# Motors.net
KiCad netlist of a schematic drawn in Altium Designer
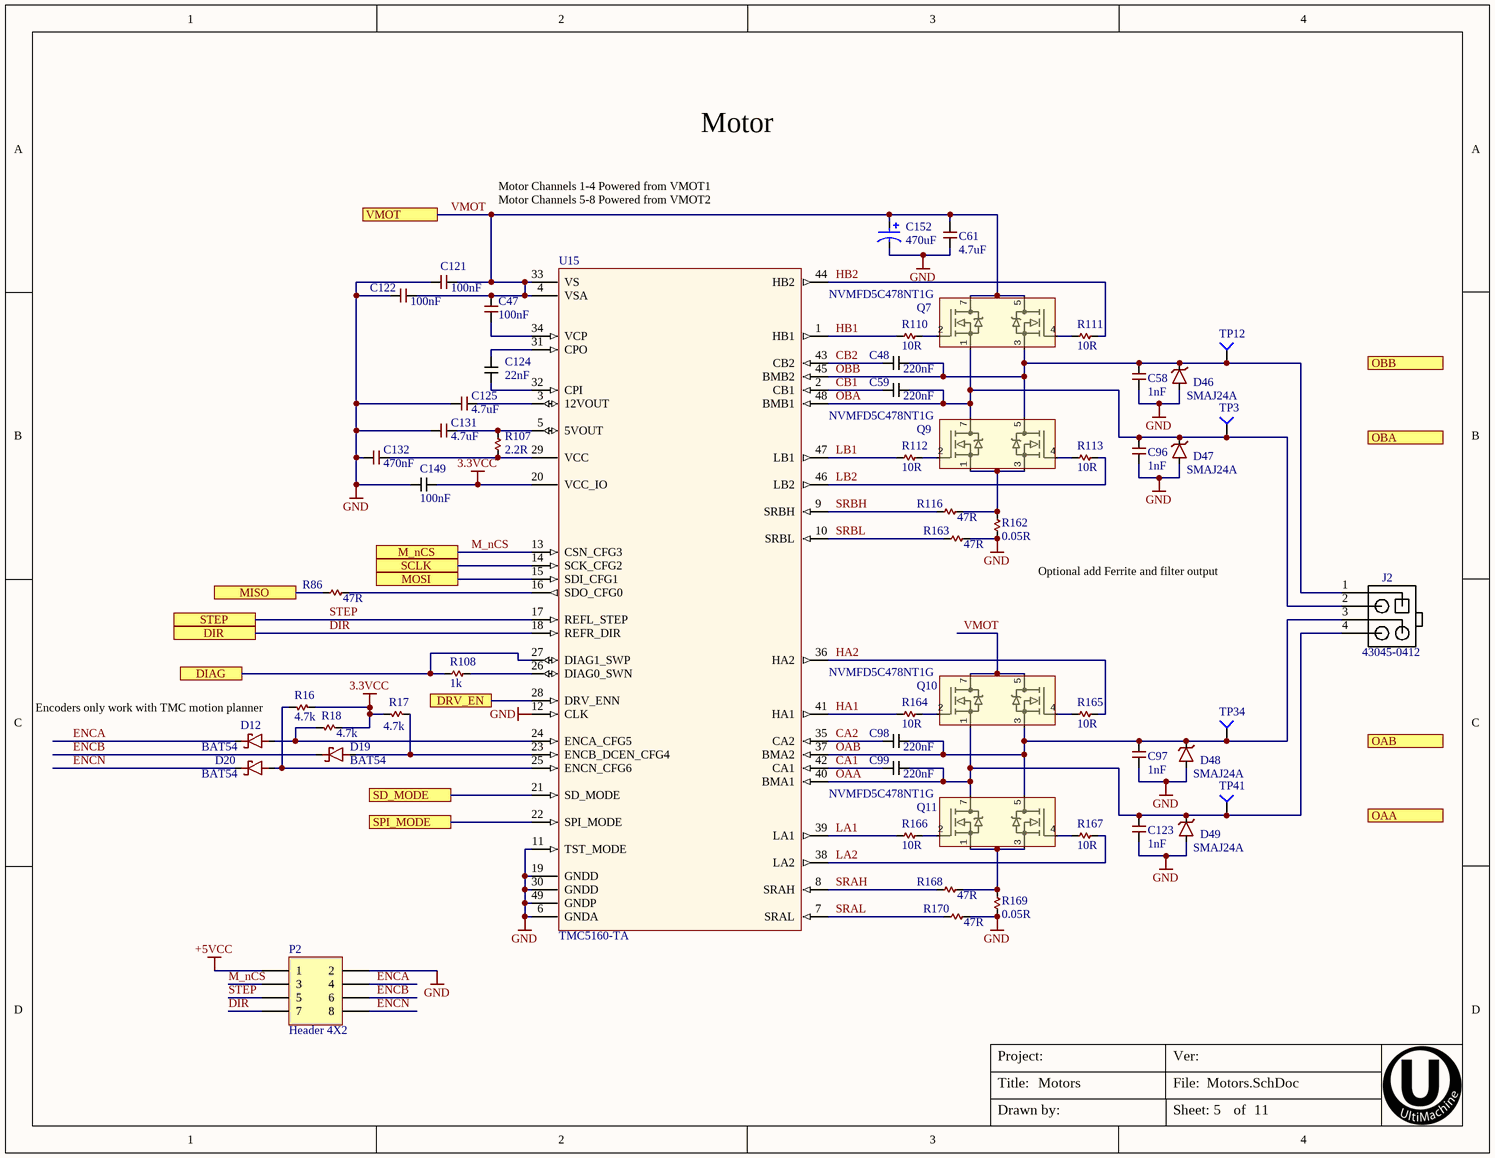
[diagram p0: Motors.SchDoc]

(export (version "E")
  (design (tool "Eeschema 10.0.6"))
  (components
    (comp (ref "C47")
      (value "100nF")
      (footprint "C0603")
      (description "CAP CER 0603 100nF 50V 10% X7R")
      (fields (field (name "MANUFACTURER") "Kemet") (field (name "PART") "C0603C104K5RACTU"))
      (libsource (lib "Capacitors") (part "100nF 0603 50V X7R"))
    )
    (comp (ref "C48")
      (value "220nF")
      (footprint "C0603")
      (description "CAP CER 0.22UF 50V X7R 0603")
      (fields (field (name "MANUFACTURER") "TDK") (field (name "PART") "CGA3E3X7R1H224K080AB"))
      (libsource (lib "Capacitors") (part "220nF 50V X7R 0603"))
    )
    (comp (ref "C58")
      (value "1nF")
      (footprint "C0603")
      (description "CAP CER 0603  1nF 50v 10% X7R")
      (fields (field (name "MANUFACTURER") "Kemet") (field (name "PART") "C0603C102K5RACTU"))
      (libsource (lib "Capacitors") (part "1nF 50V X7R 0603"))
    )
    (comp (ref "C59")
      (value "220nF")
      (footprint "C0603")
      (description "CAP CER 0.22UF 50V X7R 0603")
      (fields (field (name "MANUFACTURER") "TDK") (field (name "PART") "CGA3E3X7R1H224K080AB"))
      (libsource (lib "Capacitors") (part "220nF 50V X7R 0603"))
    )
    (comp (ref "C61")
      (value "4.7uF")
      (footprint "C1206")
      (description "CAP CER 1206 4.7uF 50V 10% X5R")
      (fields (field (name "MANUFACTURER") "Kemet") (field (name "PART") "C1206C475K5PACTU"))
      (libsource (lib "Capacitors") (part "4.7uF 1206 50V X5R"))
    )
    (comp (ref "C96")
      (value "1nF")
      (footprint "C0603")
      (description "CAP CER 0603  1nF 50v 10% X7R")
      (fields (field (name "MANUFACTURER") "Kemet") (field (name "PART") "C0603C102K5RACTU"))
      (libsource (lib "Capacitors") (part "1nF 50V X7R 0603"))
    )
    (comp (ref "C97")
      (value "1nF")
      (footprint "C0603")
      (description "CAP CER 0603  1nF 50v 10% X7R")
      (fields (field (name "MANUFACTURER") "Kemet") (field (name "PART") "C0603C102K5RACTU"))
      (libsource (lib "Capacitors") (part "1nF 50V X7R 0603"))
    )
    (comp (ref "C98")
      (value "220nF")
      (footprint "C0603")
      (description "CAP CER 0.22UF 50V X7R 0603")
      (fields (field (name "MANUFACTURER") "TDK") (field (name "PART") "CGA3E3X7R1H224K080AB"))
      (libsource (lib "Capacitors") (part "220nF 50V X7R 0603"))
    )
    (comp (ref "C99")
      (value "220nF")
      (footprint "C0603")
      (description "CAP CER 0.22UF 50V X7R 0603")
      (fields (field (name "MANUFACTURER") "TDK") (field (name "PART") "CGA3E3X7R1H224K080AB"))
      (libsource (lib "Capacitors") (part "220nF 50V X7R 0603"))
    )
    (comp (ref "C121")
      (value "100nF")
      (footprint "C0603")
      (description "CAP CER 0603 100nF 50V 10% X7R")
      (fields (field (name "MANUFACTURER") "Kemet") (field (name "PART") "C0603C104K5RACTU"))
      (libsource (lib "Capacitors") (part "100nF 0603 50V X7R"))
    )
    (comp (ref "C122")
      (value "100nF")
      (footprint "C0603")
      (description "CAP CER 0603 100nF 50V 10% X7R")
      (fields (field (name "MANUFACTURER") "Kemet") (field (name "PART") "C0603C104K5RACTU"))
      (libsource (lib "Capacitors") (part "100nF 0603 50V X7R"))
    )
    (comp (ref "C123")
      (value "1nF")
      (footprint "C0603")
      (description "CAP CER 0603  1nF 50v 10% X7R")
      (fields (field (name "MANUFACTURER") "Kemet") (field (name "PART") "C0603C102K5RACTU"))
      (libsource (lib "Capacitors") (part "1nF 50V X7R 0603"))
    )
    (comp (ref "C124")
      (value "22nF")
      (footprint "C0603")
      (description "CAP CER 0.022UF 100V X7R 0603")
      (fields (field (name "MANUFACTURER") "Kemet") (field (name "PART") "C0603C223K1RACTU"))
      (libsource (lib "Capacitors") (part "22nF 100V X7R 0603"))
    )
    (comp (ref "C125")
      (value "4.7uF")
      (footprint "C1206")
      (description "CAP CER 1206 4.7uF 50V 10% X5R")
      (fields (field (name "MANUFACTURER") "Kemet") (field (name "PART") "C1206C475K5PACTU"))
      (libsource (lib "Capacitors") (part "4.7uF 1206 50V X5R"))
    )
    (comp (ref "C131")
      (value "4.7uF")
      (footprint "C0603")
      (description "CAP CER 4.7UF 6.3V X7R 0603")
      (fields (field (name "MANUFACTURER") "Samsung") (field (name "PART") "CL10B475KQ8NQNC"))
      (libsource (lib "Capacitors") (part "4.7uF 0603 6.3V X7R"))
    )
    (comp (ref "C132")
      (value "470nF")
      (footprint "C0402")
      (description "470nF 6.3v C0402 - GRM155R60J474KE19D")
      (fields (field (name "TOLERANCE") "10%") (field (name "MANUFACTURER") "Murata"))
      (libsource (lib "Capacitors") (part "470nF 0402 6.3V X5R"))
    )
    (comp (ref "C149")
      (value "100nF")
      (footprint "C0201 Large Pads")
      (description "CAP CER 0.1UF 6.3V 10% X5R 0201")
      (fields (field (name "MANUFACTURER") "Samsung") (field (name "TOLERANCE") "10%"))
      (libsource (lib "Capacitors") (part "100nF 6.3V X5R 0201"))
    )
    (comp (ref "C152")
      (value "470uF")
      (footprint "CAP16x17")
      (description "CAP ALUM 470UF 20% 50V SMD")
      (fields (field (name "MANUFACTURER") "Nichicon") (field (name "PART") "UCZ1H471MNQ1MS"))
      (libsource (lib "Capacitors") (part "470uF Al-El 50V 80mOhms 16-18mmD"))
    )
    (comp (ref "D12")
      (value "BAT54")
      (footprint "SOD523_IPC")
      (description "DIODE SCHOTTKY 30V 200MA SOD523")
      (fields (field (name "MANUFACTURER") "Diodes Incorporated") (field (name "PART") "BAT54WX-TP"))
      (libsource (lib "Diodes") (part "BAT54WX"))
    )
    (comp (ref "D19")
      (value "BAT54")
      (footprint "SOD523_IPC")
      (description "DIODE SCHOTTKY 30V 200MA SOD523")
      (fields (field (name "MANUFACTURER") "Diodes Incorporated") (field (name "PART") "BAT54WX-TP"))
      (libsource (lib "Diodes") (part "BAT54WX"))
    )
    (comp (ref "D20")
      (value "BAT54")
      (footprint "SOD523_IPC")
      (description "DIODE SCHOTTKY 30V 200MA SOD523")
      (fields (field (name "MANUFACTURER") "Diodes Incorporated") (field (name "PART") "BAT54WX-TP"))
      (libsource (lib "Diodes") (part "BAT54WX"))
    )
    (comp (ref "D46")
      (value "SMAJ24A")
      (footprint "SMA-SM")
      (description "TVS DIODE 24V 38.9V SMA")
      (fields (field (name "MANUFACTURER") "Bourns Inc"))
      (libsource (lib "Diodes") (part "SMAJ24A"))
    )
    (comp (ref "D47")
      (value "SMAJ24A")
      (footprint "SMA-SM")
      (description "TVS DIODE 24V 38.9V SMA")
      (fields (field (name "MANUFACTURER") "Bourns Inc"))
      (libsource (lib "Diodes") (part "SMAJ24A"))
    )
    (comp (ref "D48")
      (value "SMAJ24A")
      (footprint "SMA-SM")
      (description "TVS DIODE 24V 38.9V SMA")
      (fields (field (name "MANUFACTURER") "Bourns Inc"))
      (libsource (lib "Diodes") (part "SMAJ24A"))
    )
    (comp (ref "D49")
      (value "SMAJ24A")
      (footprint "SMA-SM")
      (description "TVS DIODE 24V 38.9V SMA")
      (fields (field (name "MANUFACTURER") "Bourns Inc"))
      (libsource (lib "Diodes") (part "SMAJ24A"))
    )
    (comp (ref "J2")
      (value "43045-0412")
      (footprint "43045-0412")
      (description "Conn - 3mm Pitch Fixed")
      (fields (field (name "MANUFACTURER") "Molex"))
      (libsource (lib "Connectors") (part "Micro-Fit THT 4pos 3mm"))
    )
    (comp (ref "P2")
      (value "Header 4X2")
      (footprint "HDR2X4")
      (description "Header, 4-Pin, Dual row")
      (fields (field (name "PUBLISHER") "Altium Limited"))
      (libsource (lib "Miscellaneous Connectors") (part "Header 4X2"))
    )
    (comp (ref "Q7")
      (value "NVMFD5C478NT1G")
      (footprint "SO8FL-Dual (DFN8 5x6, 1.26P Dual Flag)")
      (description "40V 17 MOHM T6 S08FL DUAL")
      (fields (field (name "MANUFACTURER") "ON Semiconductor") (field (name "TOLERANCE") "-NA-"))
      (libsource (lib "Transistors") (part "NVMFD5C478NT1G"))
    )
    (comp (ref "Q9")
      (value "NVMFD5C478NT1G")
      (footprint "SO8FL-Dual (DFN8 5x6, 1.26P Dual Flag)")
      (description "40V 17 MOHM T6 S08FL DUAL")
      (fields (field (name "MANUFACTURER") "ON Semiconductor") (field (name "TOLERANCE") "-NA-"))
      (libsource (lib "Transistors") (part "NVMFD5C478NT1G"))
    )
    (comp (ref "Q10")
      (value "NVMFD5C478NT1G")
      (footprint "SO8FL-Dual (DFN8 5x6, 1.26P Dual Flag)")
      (description "40V 17 MOHM T6 S08FL DUAL")
      (fields (field (name "MANUFACTURER") "ON Semiconductor") (field (name "TOLERANCE") "-NA-"))
      (libsource (lib "Transistors") (part "NVMFD5C478NT1G"))
    )
    (comp (ref "Q11")
      (value "NVMFD5C478NT1G")
      (footprint "SO8FL-Dual (DFN8 5x6, 1.26P Dual Flag)")
      (description "40V 17 MOHM T6 S08FL DUAL")
      (fields (field (name "MANUFACTURER") "ON Semiconductor") (field (name "TOLERANCE") "-NA-"))
      (libsource (lib "Transistors") (part "NVMFD5C478NT1G"))
    )
    (comp (ref "R16")
      (value "4.7k")
      (footprint "R0402")
      (description "RES SMD 4.7K OHM 1% 1/16W 0402")
      (fields (field (name "MANUFACTURER") "YAGEO") (field (name "PART") "RC0402FR-074K7L"))
      (libsource (lib "Resistors") (part "4.7k 1% 0402"))
    )
    (comp (ref "R17")
      (value "4.7k")
      (footprint "R0402")
      (description "RES SMD 4.7K OHM 1% 1/16W 0402")
      (fields (field (name "MANUFACTURER") "YAGEO") (field (name "PART") "RC0402FR-074K7L"))
      (libsource (lib "Resistors") (part "4.7k 1% 0402"))
    )
    (comp (ref "R18")
      (value "4.7k")
      (footprint "R0402")
      (description "RES SMD 4.7K OHM 1% 1/16W 0402")
      (fields (field (name "MANUFACTURER") "YAGEO") (field (name "PART") "RC0402FR-074K7L"))
      (libsource (lib "Resistors") (part "4.7k 1% 0402"))
    )
    (comp (ref "R86")
      (value "47R")
      (footprint "R0402")
      (description "RES 47 OHM 1% 1/16W 0402")
      (fields (field (name "MANUFACTURER") "Vishay Dale") (field (name "TOLERANCE") "+/- 1%"))
      (libsource (lib "Resistors") (part "47R 1% 0402"))
    )
    (comp (ref "R107")
      (value "2.2R")
      (footprint "R0402")
      (description "RES SMD 2.2 OHM 5% 1/16W 0402")
      (fields (field (name "MANUFACTURER") "Yageo") (field (name "TOLERANCE") "+/- 5%"))
      (libsource (lib "Resistors") (part "2.2R 5% 0402"))
    )
    (comp (ref "R108")
      (value "1k")
      (footprint "R0402")
      (description "RES 0402 1k 63mW 1%")
      (fields (field (name "MANUFACTURER") "Yageo") (field (name "PART") "RC0402FR-071KL"))
      (libsource (lib "Resistors") (part "1k 1% 0402"))
    )
    (comp (ref "R110")
      (value "10R")
      (footprint "R0402")
      (description "RES SMD 10 OHM 1% 1/16W 0402")
      (fields (field (name "MANUFACTURER") "Yageo") (field (name "PART") "RC0402FR-0710RL"))
      (libsource (lib "Resistors") (part "10R 1% 0402"))
    )
    (comp (ref "R111")
      (value "10R")
      (footprint "R0402")
      (description "RES SMD 10 OHM 1% 1/16W 0402")
      (fields (field (name "MANUFACTURER") "Yageo") (field (name "PART") "RC0402FR-0710RL"))
      (libsource (lib "Resistors") (part "10R 1% 0402"))
    )
    (comp (ref "R112")
      (value "10R")
      (footprint "R0402")
      (description "RES SMD 10 OHM 1% 1/16W 0402")
      (fields (field (name "MANUFACTURER") "Yageo") (field (name "PART") "RC0402FR-0710RL"))
      (libsource (lib "Resistors") (part "10R 1% 0402"))
    )
    (comp (ref "R113")
      (value "10R")
      (footprint "R0402")
      (description "RES SMD 10 OHM 1% 1/16W 0402")
      (fields (field (name "MANUFACTURER") "Yageo") (field (name "PART") "RC0402FR-0710RL"))
      (libsource (lib "Resistors") (part "10R 1% 0402"))
    )
    (comp (ref "R116")
      (value "47R")
      (footprint "R0402")
      (description "RES 47 OHM 1% 1/16W 0402")
      (fields (field (name "MANUFACTURER") "Vishay Dale") (field (name "TOLERANCE") "+/- 1%"))
      (libsource (lib "Resistors") (part "47R 1% 0402"))
    )
    (comp (ref "R162")
      (value "0.05R")
      (footprint "R2512")
      (description "RES 0.05 OHM 1% 2W 2512")
      (fields (field (name "MANUFACTURER") "Stackpole") (field (name "TOLERANCE") "+/- 1%"))
      (libsource (lib "Resistors") (part "0.05R 1% 2512"))
    )
    (comp (ref "R163")
      (value "47R")
      (footprint "R0402")
      (description "RES 47 OHM 1% 1/16W 0402")
      (fields (field (name "MANUFACTURER") "Vishay Dale") (field (name "TOLERANCE") "+/- 1%"))
      (libsource (lib "Resistors") (part "47R 1% 0402"))
    )
    (comp (ref "R164")
      (value "10R")
      (footprint "R0402")
      (description "RES SMD 10 OHM 1% 1/16W 0402")
      (fields (field (name "MANUFACTURER") "Yageo") (field (name "PART") "RC0402FR-0710RL"))
      (libsource (lib "Resistors") (part "10R 1% 0402"))
    )
    (comp (ref "R165")
      (value "10R")
      (footprint "R0402")
      (description "RES SMD 10 OHM 1% 1/16W 0402")
      (fields (field (name "MANUFACTURER") "Yageo") (field (name "PART") "RC0402FR-0710RL"))
      (libsource (lib "Resistors") (part "10R 1% 0402"))
    )
    (comp (ref "R166")
      (value "10R")
      (footprint "R0402")
      (description "RES SMD 10 OHM 1% 1/16W 0402")
      (fields (field (name "MANUFACTURER") "Yageo") (field (name "PART") "RC0402FR-0710RL"))
      (libsource (lib "Resistors") (part "10R 1% 0402"))
    )
    (comp (ref "R167")
      (value "10R")
      (footprint "R0402")
      (description "RES SMD 10 OHM 1% 1/16W 0402")
      (fields (field (name "MANUFACTURER") "Yageo") (field (name "PART") "RC0402FR-0710RL"))
      (libsource (lib "Resistors") (part "10R 1% 0402"))
    )
    (comp (ref "R168")
      (value "47R")
      (footprint "R0402")
      (description "RES 47 OHM 1% 1/16W 0402")
      (fields (field (name "MANUFACTURER") "Vishay Dale") (field (name "TOLERANCE") "+/- 1%"))
      (libsource (lib "Resistors") (part "47R 1% 0402"))
    )
    (comp (ref "R169")
      (value "0.05R")
      (footprint "R2512")
      (description "RES 0.05 OHM 1% 2W 2512")
      (fields (field (name "MANUFACTURER") "Stackpole") (field (name "TOLERANCE") "+/- 1%"))
      (libsource (lib "Resistors") (part "0.05R 1% 2512"))
    )
    (comp (ref "R170")
      (value "47R")
      (footprint "R0402")
      (description "RES 47 OHM 1% 1/16W 0402")
      (fields (field (name "MANUFACTURER") "Vishay Dale") (field (name "TOLERANCE") "+/- 1%"))
      (libsource (lib "Resistors") (part "47R 1% 0402"))
    )
    (comp (ref "TP3")
      (value "TP4")
      (footprint "TP-2")
      (description "Socket")
      (fields (field (name "PART") "NOTAPART-Testpoint"))
      (libsource (lib "Archim") (part "Socket"))
    )
    (comp (ref "TP12")
      (value "TP4")
      (footprint "TP-2")
      (description "Socket")
      (fields (field (name "PART") "NOTAPART-Testpoint"))
      (libsource (lib "Archim") (part "Socket"))
    )
    (comp (ref "TP34")
      (value "TP4")
      (footprint "TP-2")
      (description "Socket")
      (fields (field (name "PART") "NOTAPART-Testpoint"))
      (libsource (lib "Archim") (part "Socket"))
    )
    (comp (ref "TP41")
      (value "TP4")
      (footprint "TP-2")
      (description "Socket")
      (fields (field (name "PART") "NOTAPART-Testpoint"))
      (libsource (lib "Archim") (part "Socket"))
    )
    (comp (ref "U15")
      (value "TMC5160-TA")
      (footprint "TQFP48-EP")
      (description "IC STEPPER MOTOR DVR TQFP48-EP")
      (fields (field (name "MANUFACTURER") "Trinamic"))
      (libsource (lib "ICs-Motor Controller") (part "TMC5160-TA"))
    )
  )
  (nets
    (net (code "1") (name "+5VCC") (class "Default")
      (node (ref "P2") (pin "1") (pinfunction "1_1") (pintype "passive"))
    )
    (net (code "2") (name "/CA1") (class "Default")
      (node (ref "C99") (pin "1") (pinfunction "1_1") (pintype "passive"))
      (node (ref "U15") (pin "42") (pinfunction "CA1_42") (pintype "input"))
    )
    (net (code "3") (name "/CA2") (class "Default")
      (node (ref "C98") (pin "1") (pinfunction "1_1") (pintype "passive"))
      (node (ref "U15") (pin "35") (pinfunction "CA2_35") (pintype "input"))
    )
    (net (code "4") (name "/CB1") (class "Default")
      (node (ref "C59") (pin "1") (pinfunction "1_1") (pintype "passive"))
      (node (ref "U15") (pin "2") (pinfunction "CB1_2") (pintype "input"))
    )
    (net (code "5") (name "/CB2") (class "Default")
      (node (ref "C48") (pin "1") (pinfunction "1_1") (pintype "passive"))
      (node (ref "U15") (pin "43") (pinfunction "CB2_43") (pintype "input"))
    )
    (net (code "6") (name "/DIAG") (class "Default")
      (node (ref "R108") (pin "2") (pinfunction "2_2") (pintype "passive"))
      (node (ref "U15") (pin "27") (pinfunction "DIAG1_SWP_27") (pintype "bidirectional"))
    )
    (net (code "7") (name "/DIR") (class "Default")
      (node (ref "P2") (pin "7") (pinfunction "7_7") (pintype "passive"))
      (node (ref "U15") (pin "18") (pinfunction "REFR_DIR_18") (pintype "input"))
    )
    (net (code "8") (name "/DRV_EN") (class "Default")
      (node (ref "U15") (pin "28") (pinfunction "DRV_ENN_28") (pintype "input"))
    )
    (net (code "9") (name "/ENCA") (class "Default")
      (node (ref "D12") (pin "K") (pinfunction "K_K") (pintype "passive"))
      (node (ref "P2") (pin "4") (pinfunction "4_4") (pintype "passive"))
    )
    (net (code "10") (name "/ENCB") (class "Default")
      (node (ref "D19") (pin "K") (pinfunction "K_K") (pintype "passive"))
      (node (ref "P2") (pin "6") (pinfunction "6_6") (pintype "passive"))
    )
    (net (code "11") (name "/ENCN") (class "Default")
      (node (ref "D20") (pin "K") (pinfunction "K_K") (pintype "passive"))
      (node (ref "P2") (pin "8") (pinfunction "8_8") (pintype "passive"))
    )
    (net (code "12") (name "/HA1") (class "Default")
      (node (ref "R164") (pin "1") (pinfunction "1_1") (pintype "passive"))
      (node (ref "U15") (pin "41") (pinfunction "HA1_41") (pintype "output"))
    )
    (net (code "13") (name "/HA2") (class "Default")
      (node (ref "R165") (pin "2") (pinfunction "2_2") (pintype "passive"))
      (node (ref "U15") (pin "36") (pinfunction "HA2_36") (pintype "output"))
    )
    (net (code "14") (name "/HB1") (class "Default")
      (node (ref "R110") (pin "1") (pinfunction "1_1") (pintype "passive"))
      (node (ref "U15") (pin "1") (pinfunction "HB1_1") (pintype "output"))
    )
    (net (code "15") (name "/HB2") (class "Default")
      (node (ref "R111") (pin "2") (pinfunction "2_2") (pintype "passive"))
      (node (ref "U15") (pin "44") (pinfunction "HB2_44") (pintype "output"))
    )
    (net (code "16") (name "/LA1") (class "Default")
      (node (ref "R166") (pin "1") (pinfunction "1_1") (pintype "passive"))
      (node (ref "U15") (pin "39") (pinfunction "LA1_39") (pintype "output"))
    )
    (net (code "17") (name "/LA2") (class "Default")
      (node (ref "R167") (pin "2") (pinfunction "2_2") (pintype "passive"))
      (node (ref "U15") (pin "38") (pinfunction "LA2_38") (pintype "output"))
    )
    (net (code "18") (name "/LB1") (class "Default")
      (node (ref "R112") (pin "1") (pinfunction "1_1") (pintype "passive"))
      (node (ref "U15") (pin "47") (pinfunction "LB1_47") (pintype "output"))
    )
    (net (code "19") (name "/LB2") (class "Default")
      (node (ref "R113") (pin "2") (pinfunction "2_2") (pintype "passive"))
      (node (ref "U15") (pin "46") (pinfunction "LB2_46") (pintype "output"))
    )
    (net (code "20") (name "/MISO") (class "Default")
      (node (ref "R86") (pin "1") (pinfunction "1_1") (pintype "passive"))
    )
    (net (code "21") (name "/MOSI") (class "Default")
      (node (ref "U15") (pin "15") (pinfunction "SDI_CFG1_15") (pintype "input"))
    )
    (net (code "22") (name "/M_nCS") (class "Default")
      (node (ref "P2") (pin "3") (pinfunction "3_3") (pintype "passive"))
      (node (ref "U15") (pin "13") (pinfunction "CSN_CFG3_13") (pintype "input"))
    )
    (net (code "23") (name "/OAA") (class "Default")
      (node (ref "C123") (pin "2") (pinfunction "2_2") (pintype "passive"))
      (node (ref "C99") (pin "2") (pinfunction "2_2") (pintype "passive"))
      (node (ref "D49") (pin "K") (pinfunction "K_K") (pintype "passive"))
      (node (ref "J2") (pin "4") (pinfunction "4_4") (pintype "power_in"))
      (node (ref "Q10") (pin "1") (pinfunction "S2_1") (pintype "passive"))
      (node (ref "Q11") (pin "7") (pinfunction "D2_7") (pintype "passive"))
      (node (ref "TP41") (pin "1") (pinfunction "1_1") (pintype "passive"))
      (node (ref "U15") (pin "40") (pinfunction "BMA1_40") (pintype "input"))
    )
    (net (code "24") (name "/OAB") (class "Default")
      (node (ref "C97") (pin "2") (pinfunction "2_2") (pintype "passive"))
      (node (ref "C98") (pin "2") (pinfunction "2_2") (pintype "passive"))
      (node (ref "D48") (pin "K") (pinfunction "K_K") (pintype "passive"))
      (node (ref "J2") (pin "3") (pinfunction "3_3") (pintype "power_in"))
      (node (ref "Q10") (pin "3") (pinfunction "S1_3") (pintype "passive"))
      (node (ref "Q11") (pin "5") (pinfunction "D1_5") (pintype "passive"))
      (node (ref "TP34") (pin "1") (pinfunction "1_1") (pintype "passive"))
      (node (ref "U15") (pin "37") (pinfunction "BMA2_37") (pintype "input"))
    )
    (net (code "25") (name "/OBA") (class "Default")
      (node (ref "C59") (pin "2") (pinfunction "2_2") (pintype "passive"))
      (node (ref "C96") (pin "2") (pinfunction "2_2") (pintype "passive"))
      (node (ref "D47") (pin "K") (pinfunction "K_K") (pintype "passive"))
      (node (ref "J2") (pin "2") (pinfunction "2_2") (pintype "power_in"))
      (node (ref "Q7") (pin "1") (pinfunction "S2_1") (pintype "passive"))
      (node (ref "Q9") (pin "7") (pinfunction "D2_7") (pintype "passive"))
      (node (ref "TP3") (pin "1") (pinfunction "1_1") (pintype "passive"))
      (node (ref "U15") (pin "48") (pinfunction "BMB1_48") (pintype "input"))
    )
    (net (code "26") (name "/OBB") (class "Default")
      (node (ref "C48") (pin "2") (pinfunction "2_2") (pintype "passive"))
      (node (ref "C58") (pin "2") (pinfunction "2_2") (pintype "passive"))
      (node (ref "D46") (pin "K") (pinfunction "K_K") (pintype "passive"))
      (node (ref "J2") (pin "1") (pinfunction "1_1") (pintype "power_in"))
      (node (ref "Q7") (pin "3") (pinfunction "S1_3") (pintype "passive"))
      (node (ref "Q9") (pin "5") (pinfunction "D1_5") (pintype "passive"))
      (node (ref "TP12") (pin "1") (pinfunction "1_1") (pintype "passive"))
      (node (ref "U15") (pin "45") (pinfunction "BMB2_45") (pintype "input"))
    )
    (net (code "27") (name "/SCLK") (class "Default")
      (node (ref "U15") (pin "14") (pinfunction "SCK_CFG2_14") (pintype "input"))
    )
    (net (code "28") (name "/SD_MODE") (class "Default")
      (node (ref "U15") (pin "21") (pinfunction "SD_MODE_21") (pintype "input"))
    )
    (net (code "29") (name "/SPI_MODE") (class "Default")
      (node (ref "U15") (pin "22") (pinfunction "SPI_MODE_22") (pintype "input"))
    )
    (net (code "30") (name "/SRAH") (class "Default")
      (node (ref "R168") (pin "1") (pinfunction "1_1") (pintype "passive"))
      (node (ref "U15") (pin "8") (pinfunction "SRAH_8") (pintype "input"))
    )
    (net (code "31") (name "/SRAL") (class "Default")
      (node (ref "R170") (pin "1") (pinfunction "1_1") (pintype "passive"))
      (node (ref "U15") (pin "7") (pinfunction "SRAL_7") (pintype "input"))
    )
    (net (code "32") (name "/SRBH") (class "Default")
      (node (ref "R116") (pin "1") (pinfunction "1_1") (pintype "passive"))
      (node (ref "U15") (pin "9") (pinfunction "SRBH_9") (pintype "input"))
    )
    (net (code "33") (name "/SRBL") (class "Default")
      (node (ref "R163") (pin "1") (pinfunction "1_1") (pintype "passive"))
      (node (ref "U15") (pin "10") (pinfunction "SRBL_10") (pintype "input"))
    )
    (net (code "34") (name "/STEP") (class "Default")
      (node (ref "P2") (pin "5") (pinfunction "5_5") (pintype "passive"))
      (node (ref "U15") (pin "17") (pinfunction "REFL_STEP_17") (pintype "input"))
    )
    (net (code "35") (name "/VMOT") (class "Default")
      (node (ref "C121") (pin "2") (pinfunction "2_2") (pintype "passive"))
      (node (ref "C122") (pin "2") (pinfunction "2_2") (pintype "passive"))
      (node (ref "C152") (pin "1") (pinfunction "1_1") (pintype "passive"))
      (node (ref "C47") (pin "2") (pinfunction "2_2") (pintype "passive"))
      (node (ref "C61") (pin "2") (pinfunction "2_2") (pintype "passive"))
      (node (ref "Q10") (pin "5") (pinfunction "D1_5") (pintype "passive"))
      (node (ref "Q10") (pin "7") (pinfunction "D2_7") (pintype "passive"))
      (node (ref "Q7") (pin "5") (pinfunction "D1_5") (pintype "passive"))
      (node (ref "Q7") (pin "7") (pinfunction "D2_7") (pintype "passive"))
      (node (ref "U15") (pin "33") (pinfunction "VS_33") (pintype "power_in"))
      (node (ref "U15") (pin "4") (pinfunction "VSA_4") (pintype "power_in"))
    )
    (net (code "36") (name "3.3VCC") (class "Default")
      (node (ref "C149") (pin "2") (pinfunction "2_2") (pintype "passive"))
      (node (ref "R16") (pin "2") (pinfunction "2_2") (pintype "passive"))
      (node (ref "R17") (pin "1") (pinfunction "1_1") (pintype "passive"))
      (node (ref "R18") (pin "2") (pinfunction "2_2") (pintype "passive"))
      (node (ref "U15") (pin "20") (pinfunction "VCC_IO_20") (pintype "power_in"))
    )
    (net (code "37") (name "GND") (class "Default")
      (node (ref "C121") (pin "1") (pinfunction "1_1") (pintype "passive"))
      (node (ref "C122") (pin "1") (pinfunction "1_1") (pintype "passive"))
      (node (ref "C123") (pin "1") (pinfunction "1_1") (pintype "passive"))
      (node (ref "C125") (pin "1") (pinfunction "1_1") (pintype "passive"))
      (node (ref "C131") (pin "1") (pinfunction "1_1") (pintype "passive"))
      (node (ref "C132") (pin "1") (pinfunction "1_1") (pintype "passive"))
      (node (ref "C149") (pin "1") (pinfunction "1_1") (pintype "passive"))
      (node (ref "C152") (pin "2") (pinfunction "2_2") (pintype "passive"))
      (node (ref "C58") (pin "1") (pinfunction "1_1") (pintype "passive"))
      (node (ref "C61") (pin "1") (pinfunction "1_1") (pintype "passive"))
      (node (ref "C96") (pin "1") (pinfunction "1_1") (pintype "passive"))
      (node (ref "C97") (pin "1") (pinfunction "1_1") (pintype "passive"))
      (node (ref "D46") (pin "A") (pinfunction "A_A") (pintype "passive"))
      (node (ref "D47") (pin "A") (pinfunction "A_A") (pintype "passive"))
      (node (ref "D48") (pin "A") (pinfunction "A_A") (pintype "passive"))
      (node (ref "D49") (pin "A") (pinfunction "A_A") (pintype "passive"))
      (node (ref "P2") (pin "2") (pinfunction "2_2") (pintype "passive"))
      (node (ref "R162") (pin "1") (pinfunction "1_1") (pintype "passive"))
      (node (ref "R163") (pin "2") (pinfunction "2_2") (pintype "passive"))
      (node (ref "R169") (pin "1") (pinfunction "1_1") (pintype "passive"))
      (node (ref "R170") (pin "2") (pinfunction "2_2") (pintype "passive"))
      (node (ref "U15") (pin "11") (pinfunction "TST_MODE_11") (pintype "input"))
      (node (ref "U15") (pin "12") (pinfunction "CLK_12") (pintype "input"))
      (node (ref "U15") (pin "19") (pinfunction "GNDD_19") (pintype "power_in"))
      (node (ref "U15") (pin "30") (pinfunction "GNDD_30") (pintype "power_in"))
      (node (ref "U15") (pin "49") (pinfunction "GNDP_49") (pintype "power_in"))
      (node (ref "U15") (pin "6") (pinfunction "GNDA_6") (pintype "power_in"))
    )
    (net (code "38") (name "Net-(Q7-G1)") (class "Default")
      (node (ref "Q7") (pin "4") (pinfunction "G1_4") (pintype "passive"))
      (node (ref "R111") (pin "1") (pinfunction "1_1") (pintype "passive"))
    )
    (net (code "39") (name "Net-(Q7-G2)") (class "Default")
      (node (ref "Q7") (pin "2") (pinfunction "G2_2") (pintype "passive"))
      (node (ref "R110") (pin "2") (pinfunction "2_2") (pintype "passive"))
    )
    (net (code "40") (name "Net-(Q9-G1)") (class "Default")
      (node (ref "Q9") (pin "4") (pinfunction "G1_4") (pintype "passive"))
      (node (ref "R113") (pin "1") (pinfunction "1_1") (pintype "passive"))
    )
    (net (code "41") (name "Net-(Q9-G2)") (class "Default")
      (node (ref "Q9") (pin "2") (pinfunction "G2_2") (pintype "passive"))
      (node (ref "R112") (pin "2") (pinfunction "2_2") (pintype "passive"))
    )
    (net (code "42") (name "Net-(Q9-S1)") (class "Default")
      (node (ref "Q9") (pin "1") (pinfunction "S2_1") (pintype "passive"))
      (node (ref "Q9") (pin "3") (pinfunction "S1_3") (pintype "passive"))
      (node (ref "R116") (pin "2") (pinfunction "2_2") (pintype "passive"))
      (node (ref "R162") (pin "2") (pinfunction "2_2") (pintype "passive"))
    )
    (net (code "43") (name "Net-(Q10-G1)") (class "Default")
      (node (ref "Q10") (pin "4") (pinfunction "G1_4") (pintype "passive"))
      (node (ref "R165") (pin "1") (pinfunction "1_1") (pintype "passive"))
    )
    (net (code "44") (name "Net-(Q10-G2)") (class "Default")
      (node (ref "Q10") (pin "2") (pinfunction "G2_2") (pintype "passive"))
      (node (ref "R164") (pin "2") (pinfunction "2_2") (pintype "passive"))
    )
    (net (code "45") (name "Net-(Q11-G1)") (class "Default")
      (node (ref "Q11") (pin "4") (pinfunction "G1_4") (pintype "passive"))
      (node (ref "R167") (pin "1") (pinfunction "1_1") (pintype "passive"))
    )
    (net (code "46") (name "Net-(Q11-G2)") (class "Default")
      (node (ref "Q11") (pin "2") (pinfunction "G2_2") (pintype "passive"))
      (node (ref "R166") (pin "2") (pinfunction "2_2") (pintype "passive"))
    )
    (net (code "47") (name "Net-(Q11-S1)") (class "Default")
      (node (ref "Q11") (pin "1") (pinfunction "S2_1") (pintype "passive"))
      (node (ref "Q11") (pin "3") (pinfunction "S1_3") (pintype "passive"))
      (node (ref "R168") (pin "2") (pinfunction "2_2") (pintype "passive"))
      (node (ref "R169") (pin "2") (pinfunction "2_2") (pintype "passive"))
    )
    (net (code "48") (name "Net-(U15-5VOUT)") (class "Default")
      (node (ref "C131") (pin "2") (pinfunction "2_2") (pintype "passive"))
      (node (ref "R107") (pin "2") (pinfunction "2_2") (pintype "passive"))
      (node (ref "U15") (pin "5") (pinfunction "5VOUT_5") (pintype "bidirectional"))
    )
    (net (code "49") (name "Net-(U15-12VOUT)") (class "Default")
      (node (ref "C125") (pin "2") (pinfunction "2_2") (pintype "passive"))
      (node (ref "U15") (pin "3") (pinfunction "12VOUT_3") (pintype "bidirectional"))
    )
    (net (code "50") (name "Net-(U15-CPI)") (class "Default")
      (node (ref "C124") (pin "1") (pinfunction "1_1") (pintype "passive"))
      (node (ref "U15") (pin "32") (pinfunction "CPI_32") (pintype "input"))
    )
    (net (code "51") (name "Net-(U15-CPO)") (class "Default")
      (node (ref "C124") (pin "2") (pinfunction "2_2") (pintype "passive"))
      (node (ref "U15") (pin "31") (pinfunction "CPO_31") (pintype "input"))
    )
    (net (code "52") (name "Net-(U15-DIAG0_SWN)") (class "Default")
      (node (ref "R108") (pin "1") (pinfunction "1_1") (pintype "passive"))
      (node (ref "U15") (pin "26") (pinfunction "DIAG0_SWN_26") (pintype "bidirectional"))
    )
    (net (code "53") (name "Net-(U15-ENCA_CFG5)") (class "Default")
      (node (ref "D12") (pin "A") (pinfunction "A_A") (pintype "passive"))
      (node (ref "R18") (pin "1") (pinfunction "1_1") (pintype "passive"))
      (node (ref "U15") (pin "24") (pinfunction "ENCA_CFG5_24") (pintype "input"))
    )
    (net (code "54") (name "Net-(U15-ENCB_DCEN_CFG4)") (class "Default")
      (node (ref "D19") (pin "A") (pinfunction "A_A") (pintype "passive"))
      (node (ref "R17") (pin "2") (pinfunction "2_2") (pintype "passive"))
      (node (ref "U15") (pin "23") (pinfunction "ENCB_DCEN_CFG4_23") (pintype "input"))
    )
    (net (code "55") (name "Net-(U15-ENCN_CFG6)") (class "Default")
      (node (ref "D20") (pin "A") (pinfunction "A_A") (pintype "passive"))
      (node (ref "R16") (pin "1") (pinfunction "1_1") (pintype "passive"))
      (node (ref "U15") (pin "25") (pinfunction "ENCN_CFG6_25") (pintype "input"))
    )
    (net (code "56") (name "Net-(U15-SDO_CFG0)") (class "Default")
      (node (ref "R86") (pin "2") (pinfunction "2_2") (pintype "passive"))
      (node (ref "U15") (pin "16") (pinfunction "SDO_CFG0_16") (pintype "output"))
    )
    (net (code "57") (name "Net-(U15-VCC)") (class "Default")
      (node (ref "C132") (pin "2") (pinfunction "2_2") (pintype "passive"))
      (node (ref "R107") (pin "1") (pinfunction "1_1") (pintype "passive"))
      (node (ref "U15") (pin "29") (pinfunction "VCC_29") (pintype "power_in"))
    )
    (net (code "58") (name "Net-(U15-VCP)") (class "Default")
      (node (ref "C47") (pin "1") (pinfunction "1_1") (pintype "passive"))
      (node (ref "U15") (pin "34") (pinfunction "VCP_34") (pintype "input"))
    )
  )
)
